# Communication.net
KiCad netlist of a schematic drawn in Altium Designer
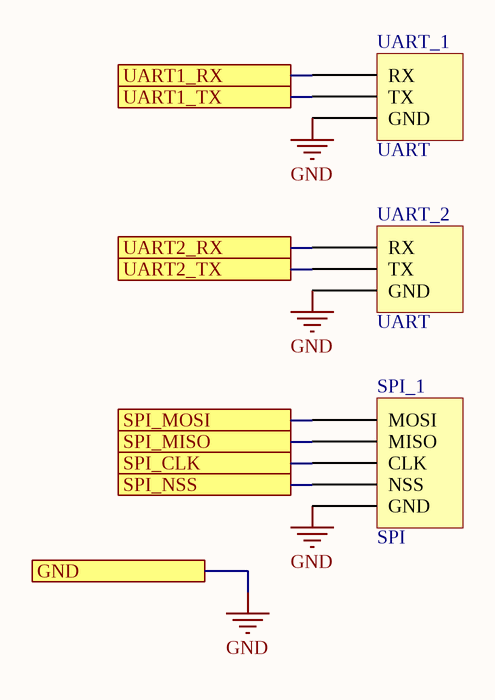
[diagram p0: Communication.SchDoc]

(export (version "E")
  (design (tool "Eeschema 10.0.6"))
  (components
    (comp (ref "SPI_1") (value "SPI") (footprint "SPI") (libsource (lib "Schlib1") (part "SPI")))
    (comp (ref "UART_1") (value "UART") (footprint "UART") (libsource (lib "Schlib1") (part "UART")))
    (comp (ref "UART_2") (value "UART") (footprint "UART") (libsource (lib "Schlib1") (part "UART")))
  )
  (nets
    (net (code "1") (name "/SPI_CLK") (class "Default")
      (node (ref "SPI_1") (pin "4") (pinfunction "CLK_4") (pintype "passive"))
    )
    (net (code "2") (name "/SPI_MISO") (class "Default")
      (node (ref "SPI_1") (pin "3") (pinfunction "MISO_3") (pintype "passive"))
    )
    (net (code "3") (name "/SPI_MOSI") (class "Default")
      (node (ref "SPI_1") (pin "2") (pinfunction "MOSI_2") (pintype "passive"))
    )
    (net (code "4") (name "/SPI_NSS") (class "Default")
      (node (ref "SPI_1") (pin "5") (pinfunction "NSS_5") (pintype "passive"))
    )
    (net (code "5") (name "/UART1_RX") (class "Default")
      (node (ref "UART_1") (pin "2") (pinfunction "RX_2") (pintype "passive"))
    )
    (net (code "6") (name "/UART1_TX") (class "Default")
      (node (ref "UART_1") (pin "3") (pinfunction "TX_3") (pintype "passive"))
    )
    (net (code "7") (name "/UART2_RX") (class "Default")
      (node (ref "UART_2") (pin "2") (pinfunction "RX_2") (pintype "passive"))
    )
    (net (code "8") (name "/UART2_TX") (class "Default")
      (node (ref "UART_2") (pin "3") (pinfunction "TX_3") (pintype "passive"))
    )
    (net (code "9") (name "GND") (class "Default")
      (node (ref "SPI_1") (pin "1") (pinfunction "GND_1") (pintype "passive"))
      (node (ref "UART_1") (pin "1") (pinfunction "GND_1") (pintype "passive"))
      (node (ref "UART_2") (pin "1") (pinfunction "GND_1") (pintype "passive"))
    )
  )
)
